# DAQ_Connector.net
KiCad netlist of a schematic drawn in Altium Designer
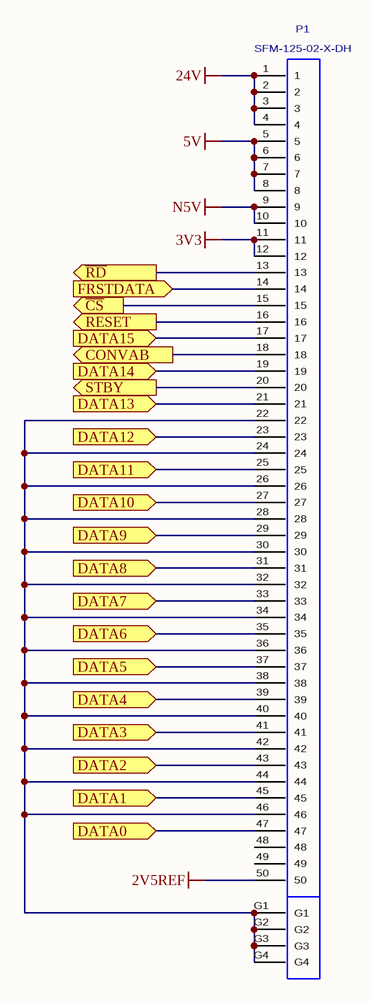
[diagram p0: DAQ Connector.SchDoc]

(export (version "E")
  (design (tool "Eeschema 10.0.6"))
  (components
    (comp (ref "P1")
      (value "SFM-125-02-X-DH")
      (footprint "SFM-125-02-X-DH")
      (description ".050\" (1,27mm) Tiger Eye Contact, Molded-to-Position Socket Strip, Double Horizontal.")
      (fields (field (name "MANUFACTURER") "SAMTEC") (field (name "CREATED") "October 28, 2015 - Wendy Xin"))
      (libsource (lib "SFM-125-02-X-DH") (part "SFM-125-02-X-DH"))
    )
  )
  (nets
    (net (code "1") (name "/CONVAB") (class "Default")
      (node (ref "P1") (pin "18") (pinfunction "18_18") (pintype "passive"))
    )
    (net (code "2") (name "/DATA0") (class "Default")
      (node (ref "P1") (pin "47") (pinfunction "47_47") (pintype "passive"))
    )
    (net (code "3") (name "/DATA1") (class "Default")
      (node (ref "P1") (pin "45") (pinfunction "45_45") (pintype "passive"))
    )
    (net (code "4") (name "/DATA2") (class "Default")
      (node (ref "P1") (pin "43") (pinfunction "43_43") (pintype "passive"))
    )
    (net (code "5") (name "/DATA3") (class "Default")
      (node (ref "P1") (pin "41") (pinfunction "41_41") (pintype "passive"))
    )
    (net (code "6") (name "/DATA4") (class "Default")
      (node (ref "P1") (pin "39") (pinfunction "39_39") (pintype "passive"))
    )
    (net (code "7") (name "/DATA5") (class "Default")
      (node (ref "P1") (pin "37") (pinfunction "37_37") (pintype "passive"))
    )
    (net (code "8") (name "/DATA6") (class "Default")
      (node (ref "P1") (pin "35") (pinfunction "35_35") (pintype "passive"))
    )
    (net (code "9") (name "/DATA7") (class "Default")
      (node (ref "P1") (pin "33") (pinfunction "33_33") (pintype "passive"))
    )
    (net (code "10") (name "/DATA8") (class "Default")
      (node (ref "P1") (pin "31") (pinfunction "31_31") (pintype "passive"))
    )
    (net (code "11") (name "/DATA9") (class "Default")
      (node (ref "P1") (pin "29") (pinfunction "29_29") (pintype "passive"))
    )
    (net (code "12") (name "/DATA10") (class "Default")
      (node (ref "P1") (pin "27") (pinfunction "27_27") (pintype "passive"))
    )
    (net (code "13") (name "/DATA11") (class "Default")
      (node (ref "P1") (pin "25") (pinfunction "25_25") (pintype "passive"))
    )
    (net (code "14") (name "/DATA12") (class "Default")
      (node (ref "P1") (pin "23") (pinfunction "23_23") (pintype "passive"))
    )
    (net (code "15") (name "/DATA13") (class "Default")
      (node (ref "P1") (pin "21") (pinfunction "21_21") (pintype "passive"))
    )
    (net (code "16") (name "/DATA14") (class "Default")
      (node (ref "P1") (pin "19") (pinfunction "19_19") (pintype "passive"))
    )
    (net (code "17") (name "/DATA15") (class "Default")
      (node (ref "P1") (pin "17") (pinfunction "17_17") (pintype "passive"))
    )
    (net (code "18") (name "/FRSTDATA") (class "Default")
      (node (ref "P1") (pin "14") (pinfunction "14_14") (pintype "passive"))
    )
    (net (code "19") (name "/RESET") (class "Default")
      (node (ref "P1") (pin "16") (pinfunction "16_16") (pintype "passive"))
    )
    (net (code "20") (name "/STBY") (class "Default")
      (node (ref "P1") (pin "20") (pinfunction "20_20") (pintype "passive"))
    )
    (net (code "21") (name "/~{CS}") (class "Default")
      (node (ref "P1") (pin "15") (pinfunction "15_15") (pintype "passive"))
    )
    (net (code "22") (name "/~{RD}") (class "Default")
      (node (ref "P1") (pin "13") (pinfunction "13_13") (pintype "passive"))
    )
    (net (code "23") (name "2V5REF") (class "Default")
      (node (ref "P1") (pin "50") (pinfunction "50_50") (pintype "passive"))
    )
    (net (code "24") (name "3V3") (class "Default")
      (node (ref "P1") (pin "11") (pinfunction "11_11") (pintype "passive"))
      (node (ref "P1") (pin "12") (pinfunction "12_12") (pintype "passive"))
    )
    (net (code "25") (name "5V") (class "Default")
      (node (ref "P1") (pin "5") (pinfunction "5_5") (pintype "passive"))
      (node (ref "P1") (pin "6") (pinfunction "6_6") (pintype "passive"))
      (node (ref "P1") (pin "7") (pinfunction "7_7") (pintype "passive"))
      (node (ref "P1") (pin "8") (pinfunction "8_8") (pintype "passive"))
    )
    (net (code "26") (name "24V") (class "Default")
      (node (ref "P1") (pin "1") (pinfunction "1_1") (pintype "passive"))
      (node (ref "P1") (pin "2") (pinfunction "2_2") (pintype "passive"))
      (node (ref "P1") (pin "3") (pinfunction "3_3") (pintype "passive"))
      (node (ref "P1") (pin "4") (pinfunction "4_4") (pintype "passive"))
    )
    (net (code "27") (name "N5V") (class "Default")
      (node (ref "P1") (pin "10") (pinfunction "10_10") (pintype "passive"))
      (node (ref "P1") (pin "9") (pinfunction "9_9") (pintype "passive"))
    )
    (net (code "28") (name "Net-(P1-Pad22)") (class "Default")
      (node (ref "P1") (pin "22") (pinfunction "22_22") (pintype "passive"))
      (node (ref "P1") (pin "24") (pinfunction "24_24") (pintype "passive"))
      (node (ref "P1") (pin "26") (pinfunction "26_26") (pintype "passive"))
      (node (ref "P1") (pin "28") (pinfunction "28_28") (pintype "passive"))
      (node (ref "P1") (pin "30") (pinfunction "30_30") (pintype "passive"))
      (node (ref "P1") (pin "32") (pinfunction "32_32") (pintype "passive"))
      (node (ref "P1") (pin "34") (pinfunction "34_34") (pintype "passive"))
      (node (ref "P1") (pin "36") (pinfunction "36_36") (pintype "passive"))
      (node (ref "P1") (pin "38") (pinfunction "38_38") (pintype "passive"))
      (node (ref "P1") (pin "40") (pinfunction "40_40") (pintype "passive"))
      (node (ref "P1") (pin "42") (pinfunction "42_42") (pintype "passive"))
      (node (ref "P1") (pin "44") (pinfunction "44_44") (pintype "passive"))
      (node (ref "P1") (pin "46") (pinfunction "46_46") (pintype "passive"))
      (node (ref "P1") (pin "G1") (pinfunction "G1_G1") (pintype "passive"))
      (node (ref "P1") (pin "G2") (pinfunction "G2_G2") (pintype "passive"))
      (node (ref "P1") (pin "G3") (pinfunction "G3_G3") (pintype "passive"))
      (node (ref "P1") (pin "G4") (pinfunction "G4_G4") (pintype "passive"))
    )
    (net (code "29") (name "unconnected-(P1-Pad48)") (class "Default")
      (node (ref "P1") (pin "48") (pinfunction "48_48") (pintype "passive"))
    )
    (net (code "30") (name "unconnected-(P1-Pad49)") (class "Default")
      (node (ref "P1") (pin "49") (pinfunction "49_49") (pintype "passive"))
    )
  )
)
